# SONOff.net
KiCad netlist of a schematic drawn in EAGLE
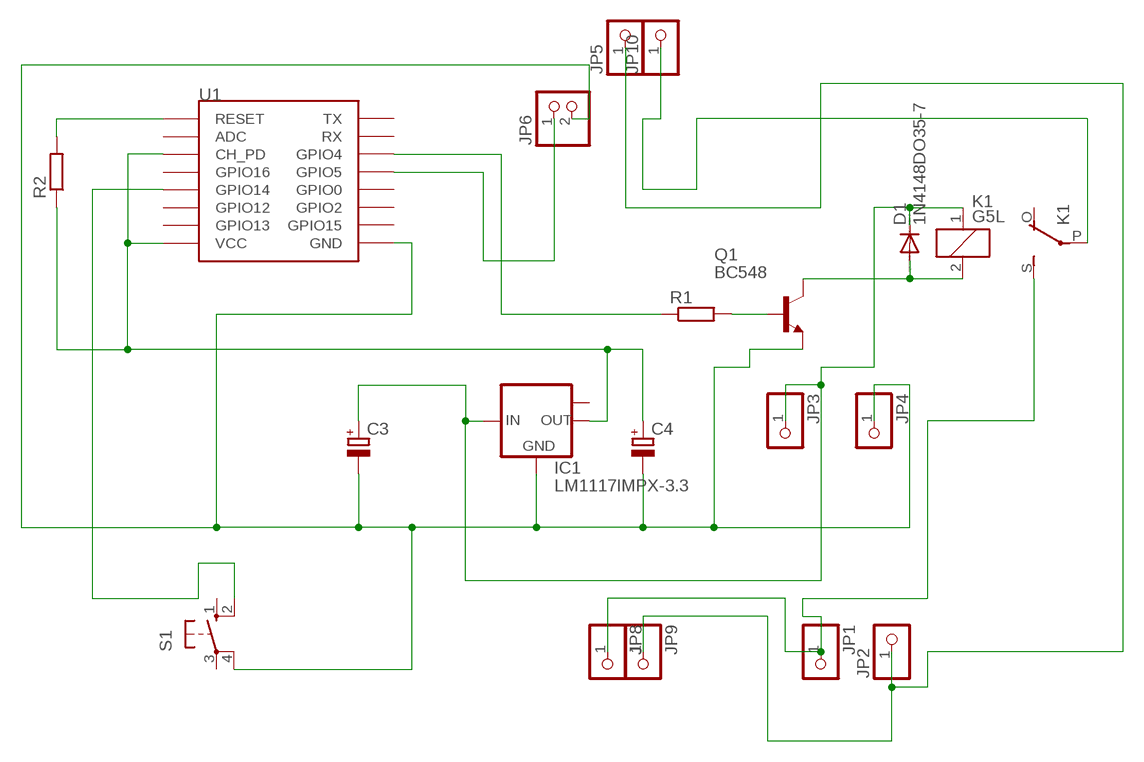
[diagram p0: schematic, sheet 1]

(export (version "E")
  (design (tool "Eeschema 10.0.6"))
  (components
    (comp (ref "C3")
      (value "CPOL-EUE3.5-8")
      (footprint "eagle-import:E3,5-8")
      (libsource (lib "eagle-import") (part "CPOL-EUE3.5-8"))
    )
    (comp (ref "C4")
      (value "CPOL-EUE2.5-5")
      (footprint "eagle-import:E2,5-5")
      (libsource (lib "eagle-import") (part "CPOL-EUE2.5-5"))
    )
    (comp (ref "D1")
      (value "1N4148DO35-7")
      (footprint "eagle-import:DO35-7")
      (libsource (lib "eagle-import") (part "1N4148DO35-7"))
    )
    (comp (ref "IC1")
      (value "LM1117IMPX-3.3")
      (footprint "eagle-import:SOT223")
      (libsource (lib "eagle-import") (part "LM1117IMPX-3.3"))
    )
    (comp (ref "JP1")
      (value "PINHD-1X1")
      (footprint "eagle-import:1X01")
      (libsource (lib "eagle-import") (part "PINHD-1X1"))
    )
    (comp (ref "JP2")
      (value "PINHD-1X1")
      (footprint "eagle-import:1X01")
      (libsource (lib "eagle-import") (part "PINHD-1X1"))
    )
    (comp (ref "JP3")
      (value "PINHD-1X1")
      (footprint "eagle-import:1X01")
      (libsource (lib "eagle-import") (part "PINHD-1X1"))
    )
    (comp (ref "JP4")
      (value "PINHD-1X1")
      (footprint "eagle-import:1X01")
      (libsource (lib "eagle-import") (part "PINHD-1X1"))
    )
    (comp (ref "JP5")
      (value "PINHD-1X1")
      (footprint "eagle-import:1X01")
      (libsource (lib "eagle-import") (part "PINHD-1X1"))
    )
    (comp (ref "JP6")
      (value "PINHD-1X2")
      (footprint "eagle-import:1X02")
      (libsource (lib "eagle-import") (part "PINHD-1X2"))
    )
    (comp (ref "JP8")
      (value "PINHD-1X1")
      (footprint "eagle-import:1X01")
      (libsource (lib "eagle-import") (part "PINHD-1X1"))
    )
    (comp (ref "JP9")
      (value "PINHD-1X1")
      (footprint "eagle-import:1X01")
      (libsource (lib "eagle-import") (part "PINHD-1X1"))
    )
    (comp (ref "JP10")
      (value "PINHD-1X1")
      (footprint "eagle-import:1X01")
      (libsource (lib "eagle-import") (part "PINHD-1X1"))
    )
    (comp (ref "K1")
      (value "G5L")
      (footprint "eagle-import:G5LE")
      (libsource (lib "eagle-import") (part "G5L"))
    )
    (comp (ref "Q1")
      (value "BC548")
      (footprint "eagle-import:TO92-EBC")
      (libsource (lib "eagle-import") (part "BC548"))
    )
    (comp (ref "R1")
      (value "R-EU_0207/10")
      (footprint "eagle-import:0207_10")
      (libsource (lib "eagle-import") (part "R-EU_0207/10"))
    )
    (comp (ref "R2")
      (value "R-EU_0207/10")
      (footprint "eagle-import:0207_10")
      (libsource (lib "eagle-import") (part "R-EU_0207/10"))
    )
    (comp (ref "S1")
      (value "10-XX")
      (footprint "eagle-import:B3F-10XX")
      (fields (field (name "MPN") "B3F-1000"))
      (libsource (lib "eagle-import") (part "10-XX"))
    )
    (comp (ref "U1")
      (value "ESP12SMD")
      (footprint "eagle-import:ESP12-SMD")
      (libsource (lib "eagle-import") (part "ESP12SMD"))
    )
  )
  (nets
    (net (code "1") (name "Net-(D1-PadA)") (class "Default")
      (node (ref "D1") (pin "A") (pinfunction "A_A") (pintype "passive"))
      (node (ref "K1") (pin "2") (pinfunction "2_2") (pintype "passive"))
      (node (ref "Q1") (pin "C") (pinfunction "C_C") (pintype "passive"))
    )
    (net (code "2") (name "Net-(IC1-GND)") (class "Default")
      (node (ref "C3") (pin "-") (pinfunction "-_-") (pintype "passive"))
      (node (ref "C4") (pin "-") (pinfunction "-_-") (pintype "passive"))
      (node (ref "IC1") (pin "1") (pinfunction "GND_1") (pintype "input"))
      (node (ref "JP4") (pin "1") (pinfunction "1_1") (pintype "passive"))
      (node (ref "JP6") (pin "2") (pinfunction "2_2") (pintype "passive"))
      (node (ref "Q1") (pin "E") (pinfunction "E_E") (pintype "passive"))
      (node (ref "S1") (pin "4") (pinfunction "P1_4") (pintype "passive"))
      (node (ref "U1") (pin "GND") (pinfunction "GND_GND") (pintype "bidirectional"))
    )
    (net (code "3") (name "Net-(IC1-IN)") (class "Default")
      (node (ref "C3") (pin "+") (pinfunction "+_+") (pintype "passive"))
      (node (ref "D1") (pin "C") (pinfunction "C_C") (pintype "passive"))
      (node (ref "IC1") (pin "3") (pinfunction "IN_3") (pintype "input"))
      (node (ref "JP3") (pin "1") (pinfunction "1_1") (pintype "passive"))
      (node (ref "K1") (pin "1") (pinfunction "1_1") (pintype "passive"))
    )
    (net (code "4") (name "Net-(IC1-OUT)") (class "Default")
      (node (ref "C4") (pin "+") (pinfunction "+_+") (pintype "passive"))
      (node (ref "IC1") (pin "2") (pinfunction "OUT_2") (pintype "passive"))
      (node (ref "R2") (pin "1") (pinfunction "1_1") (pintype "passive"))
      (node (ref "U1") (pin "CH_PD") (pinfunction "CH_PD_CH_PD") (pintype "bidirectional"))
      (node (ref "U1") (pin "VCC") (pinfunction "VCC_VCC") (pintype "bidirectional"))
    )
    (net (code "5") (name "Net-(JP1-Pad1)") (class "Default")
      (node (ref "JP1") (pin "1") (pinfunction "1_1") (pintype "passive"))
      (node (ref "JP8") (pin "1") (pinfunction "1_1") (pintype "passive"))
      (node (ref "K1") (pin "S") (pinfunction "S_S") (pintype "passive"))
    )
    (net (code "6") (name "Net-(JP2-Pad1)") (class "Default")
      (node (ref "JP2") (pin "1") (pinfunction "1_1") (pintype "passive"))
      (node (ref "JP5") (pin "1") (pinfunction "1_1") (pintype "passive"))
      (node (ref "JP9") (pin "1") (pinfunction "1_1") (pintype "passive"))
    )
    (net (code "7") (name "Net-(JP6-Pad1)") (class "Default")
      (node (ref "JP6") (pin "1") (pinfunction "1_1") (pintype "passive"))
      (node (ref "U1") (pin "GPIO5") (pinfunction "GPIO5_GPIO5") (pintype "bidirectional"))
    )
    (net (code "8") (name "Net-(JP10-Pad1)") (class "Default")
      (node (ref "JP10") (pin "1") (pinfunction "1_1") (pintype "passive"))
      (node (ref "K1") (pin "P") (pinfunction "P_P") (pintype "passive"))
    )
    (net (code "9") (name "Net-(Q1-PadB)") (class "Default")
      (node (ref "Q1") (pin "B") (pinfunction "B_B") (pintype "passive"))
      (node (ref "R1") (pin "2") (pinfunction "2_2") (pintype "passive"))
    )
    (net (code "10") (name "Net-(R1-Pad1)") (class "Default")
      (node (ref "R1") (pin "1") (pinfunction "1_1") (pintype "passive"))
      (node (ref "U1") (pin "GPIO4") (pinfunction "GPIO4_GPIO4") (pintype "bidirectional"))
    )
    (net (code "11") (name "Net-(R2-Pad2)") (class "Default")
      (node (ref "R2") (pin "2") (pinfunction "2_2") (pintype "passive"))
      (node (ref "U1") (pin "RESET") (pinfunction "RESET_RESET") (pintype "bidirectional"))
    )
    (net (code "12") (name "Net-(S1-S1)") (class "Default")
      (node (ref "S1") (pin "2") (pinfunction "S1_2") (pintype "passive"))
      (node (ref "U1") (pin "GPIO14") (pinfunction "GPIO14_GPIO14") (pintype "bidirectional"))
    )
    (net (code "13") (name "unconnected-(IC1-OUT1-PadTAB)") (class "Default")
      (node (ref "IC1") (pin "TAB") (pinfunction "OUT1_TAB") (pintype "passive"))
    )
    (net (code "14") (name "unconnected-(K1-PadO)") (class "Default")
      (node (ref "K1") (pin "O") (pinfunction "O_O") (pintype "passive"))
    )
    (net (code "15") (name "unconnected-(S1-P-Pad3)") (class "Default")
      (node (ref "S1") (pin "3") (pinfunction "P_3") (pintype "passive"))
    )
    (net (code "16") (name "unconnected-(S1-S-Pad1)") (class "Default")
      (node (ref "S1") (pin "1") (pinfunction "S_1") (pintype "passive"))
    )
    (net (code "17") (name "unconnected-(U1-PadADC)") (class "Default")
      (node (ref "U1") (pin "ADC") (pinfunction "ADC_ADC") (pintype "bidirectional"))
    )
    (net (code "18") (name "unconnected-(U1-PadGPIO0)") (class "Default")
      (node (ref "U1") (pin "GPIO0") (pinfunction "GPIO0_GPIO0") (pintype "bidirectional"))
    )
    (net (code "19") (name "unconnected-(U1-PadGPIO2)") (class "Default")
      (node (ref "U1") (pin "GPIO2") (pinfunction "GPIO2_GPIO2") (pintype "bidirectional"))
    )
    (net (code "20") (name "unconnected-(U1-PadGPIO12)") (class "Default")
      (node (ref "U1") (pin "GPIO12") (pinfunction "GPIO12_GPIO12") (pintype "bidirectional"))
    )
    (net (code "21") (name "unconnected-(U1-PadGPIO13)") (class "Default")
      (node (ref "U1") (pin "GPIO13") (pinfunction "GPIO13_GPIO13") (pintype "bidirectional"))
    )
    (net (code "22") (name "unconnected-(U1-PadGPIO15)") (class "Default")
      (node (ref "U1") (pin "GPIO15") (pinfunction "GPIO15_GPIO15") (pintype "bidirectional"))
    )
    (net (code "23") (name "unconnected-(U1-PadGPIO16)") (class "Default")
      (node (ref "U1") (pin "GPIO16") (pinfunction "GPIO16_GPIO16") (pintype "bidirectional"))
    )
    (net (code "24") (name "unconnected-(U1-RX-PadRXD0)") (class "Default")
      (node (ref "U1") (pin "RXD0") (pinfunction "RX_RXD0") (pintype "bidirectional"))
    )
    (net (code "25") (name "unconnected-(U1-TX-PadTXD0)") (class "Default")
      (node (ref "U1") (pin "TXD0") (pinfunction "TX_TXD0") (pintype "bidirectional"))
    )
  )
)
